# SUP_3_3_FMC.net
KiCad netlist of a schematic drawn in Altium Designer
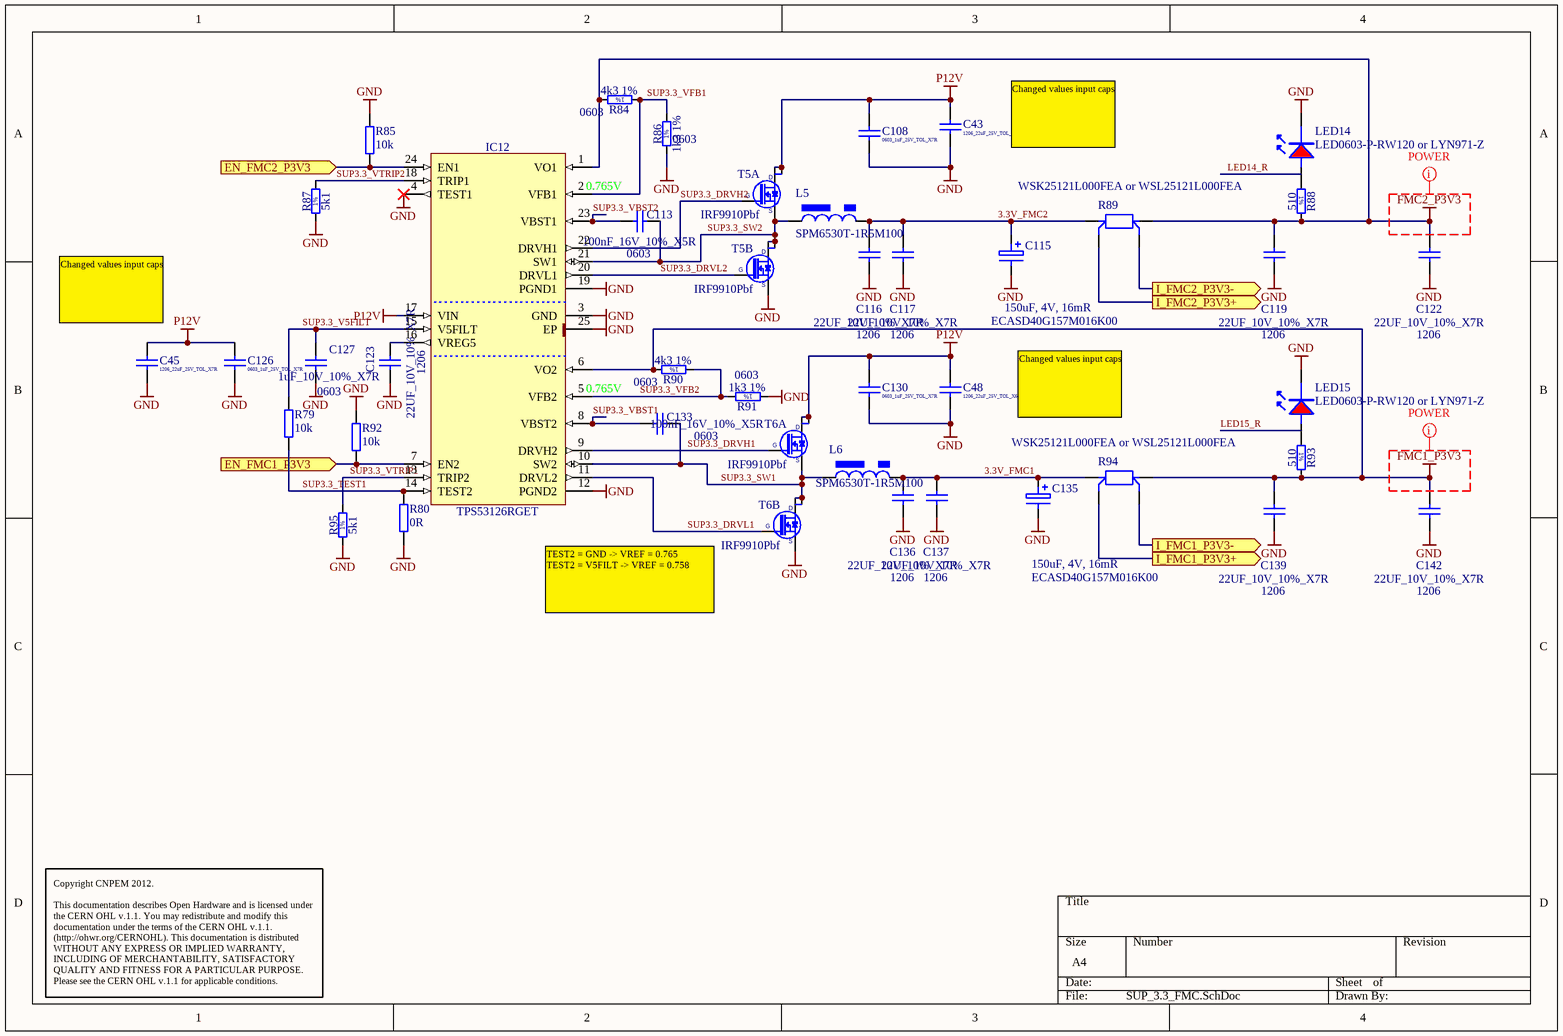
[diagram p0: SUP_3.3_FMC.SchDoc]

(export (version "E")
  (design (tool "Eeschema 10.0.6"))
  (components
    (comp (ref "C43")
      (value "1206_22uF_25V_TOL_X6S")
      (footprint "CAPC3225X140N")
      (fields (field (name "PART NUMBER") "Ceramic_1206"))
      (libsource (lib "Capacitors") (part "Capacitor"))
    )
    (comp (ref "C45")
      (value "1206_22uF_25V_TOL_X7R")
      (footprint "CAPC3225X140N")
      (fields (field (name "PART NUMBER") "Ceramic_1206"))
      (libsource (lib "Capacitors") (part "Capacitor"))
    )
    (comp (ref "C48")
      (value "1206_22uF_25V_TOL_X6S")
      (footprint "CAPC3225X140N")
      (fields (field (name "PART NUMBER") "Ceramic_1206"))
      (libsource (lib "Capacitors") (part "Capacitor"))
    )
    (comp (ref "C108")
      (value "0603_1uF_25V_TOL_X7R")
      (footprint "CAPC1608X90N")
      (fields (field (name "PART NUMBER") "Ceramic_0603"))
      (libsource (lib "Capacitors") (part "Capacitor"))
    )
    (comp (ref "C113")
      (value "100nF_16V_10%_X5R")
      (footprint "0402C")
      (description "Non-polarised capacitor")
      (fields
        (field (name "PART NUMBER") "CC0603_100NF_50V_10%_X7R")
        (field (name "VOLTAGE") "50V")
        (field (name "CASE") "0603")
        (field (name "AUTHOR") "CERN DEM JLC")
      )
      (libsource (lib "Capacitors") (part "Capacitor - non polarized"))
    )
    (comp (ref "C115")
      (value "ECASD40G157M016K00")
      (footprint "2917_POLY")
      (description "POLY, 150uF, 4V, ESR: 16mR")
      (fields (field (name "ALTIUM_VALUE") "150uF, 4V, 16mR"))
      (libsource (lib "LIBRARY_SCH") (part "CAP_POLYMER_SMDD"))
    )
    (comp (ref "C116")
      (value "22UF_10V_10%_X7R")
      (footprint "1206C")
      (description "Non-polarised capacitor")
      (fields
        (field (name "PART NUMBER") "CC1206_22UF_10V_10%_X7R")
        (field (name "VOLTAGE") "10V")
        (field (name "CASE") "1206")
        (field (name "AUTHOR") "CERN DEM JLC")
      )
      (libsource (lib "Capacitors") (part "Capacitor - non polarized"))
    )
    (comp (ref "C117")
      (value "22UF_10V_10%_X7R")
      (footprint "1206C")
      (description "Non-polarised capacitor")
      (fields
        (field (name "PART NUMBER") "CC1206_22UF_10V_10%_X7R")
        (field (name "VOLTAGE") "10V")
        (field (name "CASE") "1206")
        (field (name "AUTHOR") "CERN DEM JLC")
      )
      (libsource (lib "Capacitors") (part "Capacitor - non polarized"))
    )
    (comp (ref "C119")
      (value "22UF_10V_10%_X7R")
      (footprint "1206C")
      (description "Non-polarised capacitor")
      (fields
        (field (name "PART NUMBER") "CC1206_22UF_10V_10%_X7R")
        (field (name "VOLTAGE") "10V")
        (field (name "CASE") "1206")
        (field (name "AUTHOR") "CERN DEM JLC")
      )
      (libsource (lib "Capacitors") (part "Capacitor - non polarized"))
    )
    (comp (ref "C122")
      (value "22UF_10V_10%_X7R")
      (footprint "1206C")
      (description "Non-polarised capacitor")
      (fields
        (field (name "PART NUMBER") "CC1206_22UF_10V_10%_X7R")
        (field (name "VOLTAGE") "10V")
        (field (name "CASE") "1206")
        (field (name "AUTHOR") "CERN DEM JLC")
      )
      (libsource (lib "Capacitors") (part "Capacitor - non polarized"))
    )
    (comp (ref "C123")
      (value "22UF_10V_10%_X7R")
      (footprint "1206C")
      (description "Non-polarised capacitor")
      (fields
        (field (name "PART NUMBER") "CC1206_22UF_10V_10%_X7R")
        (field (name "VOLTAGE") "10V")
        (field (name "CASE") "1206")
        (field (name "AUTHOR") "CERN DEM JLC")
      )
      (libsource (lib "Capacitors") (part "Capacitor - non polarized"))
    )
    (comp (ref "C126")
      (value "0603_1uF_25V_TOL_X7R")
      (footprint "CAPC1608X90N")
      (fields (field (name "PART NUMBER") "Ceramic_0603"))
      (libsource (lib "Capacitors") (part "Capacitor"))
    )
    (comp (ref "C127")
      (value "1uF_10V_10%_X7R")
      (footprint "0603C")
      (description "Non-polarised capacitor")
      (fields
        (field (name "PART NUMBER") "CC0603_1UF_16V_10%_X7R")
        (field (name "VOLTAGE") "16V")
        (field (name "CASE") "0603")
        (field (name "AUTHOR") "CERN DEM JLC")
      )
      (libsource (lib "Capacitors") (part "Capacitor - non polarized"))
    )
    (comp (ref "C130")
      (value "0603_1uF_25V_TOL_X7R")
      (footprint "CAPC1608X90N")
      (fields (field (name "PART NUMBER") "Ceramic_0603"))
      (libsource (lib "Capacitors") (part "Capacitor"))
    )
    (comp (ref "C133")
      (value "100nF_16V_10%_X5R")
      (footprint "0402C")
      (description "Non-polarised capacitor")
      (fields
        (field (name "PART NUMBER") "CC0603_100NF_50V_10%_X7R")
        (field (name "VOLTAGE") "50V")
        (field (name "CASE") "0603")
        (field (name "AUTHOR") "CERN DEM JLC")
      )
      (libsource (lib "Capacitors") (part "Capacitor - non polarized"))
    )
    (comp (ref "C135")
      (value "ECASD40G157M016K00")
      (footprint "2917_POLY")
      (description "POLY, 150uF, 4V, ESR: 16mR")
      (fields (field (name "ALTIUM_VALUE") "150uF, 4V, 16mR"))
      (libsource (lib "LIBRARY_SCH") (part "CAP_POLYMER_SMDD"))
    )
    (comp (ref "C136")
      (value "22UF_10V_10%_X7R")
      (footprint "1206C")
      (description "Non-polarised capacitor")
      (fields
        (field (name "PART NUMBER") "CC1206_22UF_10V_10%_X7R")
        (field (name "VOLTAGE") "10V")
        (field (name "CASE") "1206")
        (field (name "AUTHOR") "CERN DEM JLC")
      )
      (libsource (lib "Capacitors") (part "Capacitor - non polarized"))
    )
    (comp (ref "C137")
      (value "22UF_10V_10%_X7R")
      (footprint "1206C")
      (description "Non-polarised capacitor")
      (fields
        (field (name "PART NUMBER") "CC1206_22UF_10V_10%_X7R")
        (field (name "VOLTAGE") "10V")
        (field (name "CASE") "1206")
        (field (name "AUTHOR") "CERN DEM JLC")
      )
      (libsource (lib "Capacitors") (part "Capacitor - non polarized"))
    )
    (comp (ref "C139")
      (value "22UF_10V_10%_X7R")
      (footprint "1206C")
      (description "Non-polarised capacitor")
      (fields
        (field (name "PART NUMBER") "CC1206_22UF_10V_10%_X7R")
        (field (name "VOLTAGE") "10V")
        (field (name "CASE") "1206")
        (field (name "AUTHOR") "CERN DEM JLC")
      )
      (libsource (lib "Capacitors") (part "Capacitor - non polarized"))
    )
    (comp (ref "C142")
      (value "22UF_10V_10%_X7R")
      (footprint "1206C")
      (description "Non-polarised capacitor")
      (fields
        (field (name "PART NUMBER") "CC1206_22UF_10V_10%_X7R")
        (field (name "VOLTAGE") "10V")
        (field (name "CASE") "1206")
        (field (name "AUTHOR") "CERN DEM JLC")
      )
      (libsource (lib "Capacitors") (part "Capacitor - non polarized"))
    )
    (comp (ref "IC12")
      (value "TPS53126RGET")
      (footprint "QFN50P400X400X100-25N-S255")
      (description "Dual Synchronous Step-Down Controller For Low Voltage Power Rails")
      (fields (field (name "MANUFACTURER") "TEXAS INSTRUMENTS") (field (name "AUTHOR") "CERN DEM JLC"))
      (libsource (lib "ICs And Semiconductors") (part "TPS53126RGET"))
    )
    (comp (ref "L5")
      (value "SPM6530T-1R5M100")
      (footprint "IND_TDK_SPM6530")
      (description "1.5uH, 20%, 10mR, 11.5A")
      (libsource (lib "LIBRARY_SCH") (part "L_POWER_SPM6530T"))
    )
    (comp (ref "L6")
      (value "SPM6530T-1R5M100")
      (footprint "IND_TDK_SPM6530")
      (description "1.5uH, 20%, 10mR, 11.5A")
      (libsource (lib "LIBRARY_SCH") (part "L_POWER_SPM6530T"))
    )
    (comp (ref "LED14")
      (value "LED0603-P-RW120 or LYN971-Z")
      (footprint "led_0603R")
      (description "LED 0603 red")
      (libsource (lib "LIBRARY_SCH") (part "LED_0603R"))
    )
    (comp (ref "LED15")
      (value "LED0603-P-RW120 or LYN971-Z")
      (footprint "led_0603R")
      (description "LED 0603 red")
      (libsource (lib "LIBRARY_SCH") (part "LED_0603R"))
    )
    (comp (ref "R79")
      (value "10k")
      (footprint "0402R")
      (description "SMD Resistor")
      (libsource (lib "LIBRARY_SCH") (part "RES_0402"))
    )
    (comp (ref "R80")
      (value "0R")
      (footprint "0402R")
      (description "SMD Resistor")
      (libsource (lib "LIBRARY_SCH") (part "RES_0402"))
    )
    (comp (ref "R84")
      (value "4k3 1%")
      (footprint "0603R")
      (description "Resistor - 1%")
      (fields
        (field (name "PART NUMBER") "R0603_4K3_1%_0.1W_100PPM")
        (field (name "POWER") "0.1W")
        (field (name "CASE") "0603")
        (field (name "AUTHOR") "CERN DEM JLC")
      )
      (libsource (lib "Resistors") (part "Resistor - 1%"))
    )
    (comp (ref "R85")
      (value "10k")
      (footprint "0402R")
      (description "SMD Resistor")
      (libsource (lib "LIBRARY_SCH") (part "RES_0402"))
    )
    (comp (ref "R86")
      (value "1k3 1%")
      (footprint "0603R")
      (description "Resistor - 1%")
      (fields
        (field (name "PART NUMBER") "R0603_1K3_1%_0.1W_100PPM")
        (field (name "POWER") "0.1W")
        (field (name "CASE") "0603")
        (field (name "AUTHOR") "CERN DEM JLC")
      )
      (libsource (lib "Resistors") (part "Resistor - 1%"))
    )
    (comp (ref "R87")
      (value "5k1")
      (footprint "0603R")
      (description "Resistor - 1%")
      (fields
        (field (name "PART NUMBER") "R0603_5K1_1%_0.1W_100PPM")
        (field (name "POWER") "0.1W")
        (field (name "AUTHOR") "CERN DEM JLC")
      )
      (libsource (lib "Resistors") (part "Resistor - 1%"))
    )
    (comp (ref "R88")
      (value "510")
      (footprint "0603R")
      (description "Resistor - 1%")
      (fields
        (field (name "PART NUMBER") "R0402_510R_1%_0.0625W_100PPM")
        (field (name "POWER") "0.0625W")
        (field (name "AUTHOR") "CERN DEM JLC")
      )
      (libsource (lib "Resistors") (part "Resistor - 1%"))
    )
    (comp (ref "R89")
      (value "WSK25121L000FEA or WSL25121L000FEA")
      (footprint "RES_WSK2512")
      (description "RESISTOR, METAL STRIP, 0.001 OHM 1%")
      (libsource (lib "LIBRARY_SCH") (part "RES_POW_Kelvin"))
    )
    (comp (ref "R90")
      (value "4k3 1%")
      (footprint "0603R")
      (description "Resistor - 1%")
      (fields
        (field (name "PART NUMBER") "R0603_4K3_1%_0.1W_100PPM")
        (field (name "POWER") "0.1W")
        (field (name "CASE") "0603")
        (field (name "AUTHOR") "CERN DEM JLC")
      )
      (libsource (lib "Resistors") (part "Resistor - 1%"))
    )
    (comp (ref "R91")
      (value "1k3 1%")
      (footprint "0603R")
      (description "Resistor - 1%")
      (fields
        (field (name "PART NUMBER") "R0603_1K3_1%_0.1W_100PPM")
        (field (name "POWER") "0.1W")
        (field (name "CASE") "0603")
        (field (name "AUTHOR") "CERN DEM JLC")
      )
      (libsource (lib "Resistors") (part "Resistor - 1%"))
    )
    (comp (ref "R92")
      (value "10k")
      (footprint "0402R")
      (description "SMD Resistor")
      (libsource (lib "LIBRARY_SCH") (part "RES_0402"))
    )
    (comp (ref "R93")
      (value "510")
      (footprint "0603R")
      (description "Resistor - 1%")
      (fields
        (field (name "PART NUMBER") "R0402_510R_1%_0.0625W_100PPM")
        (field (name "POWER") "0.0625W")
        (field (name "AUTHOR") "CERN DEM JLC")
      )
      (libsource (lib "Resistors") (part "Resistor - 1%"))
    )
    (comp (ref "R94")
      (value "WSK25121L000FEA or WSL25121L000FEA")
      (footprint "RES_WSK2512")
      (description "RESISTOR, METAL STRIP, 0.001 OHM 1%")
      (libsource (lib "LIBRARY_SCH") (part "RES_POW_Kelvin"))
    )
    (comp (ref "R95")
      (value "5k1")
      (footprint "0603R")
      (description "Resistor - 1%")
      (fields
        (field (name "PART NUMBER") "R0603_5K1_1%_0.1W_100PPM")
        (field (name "POWER") "0.1W")
        (field (name "AUTHOR") "CERN DEM JLC")
      )
      (libsource (lib "Resistors") (part "Resistor - 1%"))
    )
    (comp (ref "T5")
      (value "IRF9910Pbf")
      (footprint "SOIC127P600X175-8N")
      (description "Dual SO-8 MOSFET For POL Cconverter")
      (fields (field (name "MANUFACTURER") "INTERNATIONAL RECTIFIER") (field (name "AUTHOR") "CERN DEM JLC"))
      (libsource (lib "ICs And Semiconductors") (part "IRF9910"))
    )
    (comp (ref "T6")
      (value "IRF9910Pbf")
      (footprint "SOIC127P600X175-8N")
      (description "Dual SO-8 MOSFET For POL Cconverter")
      (fields (field (name "MANUFACTURER") "INTERNATIONAL RECTIFIER") (field (name "AUTHOR") "CERN DEM JLC"))
      (libsource (lib "ICs And Semiconductors") (part "IRF9910"))
    )
  )
  (nets
    (net (code "1") (name "/3.3V_FMC1") (class "Default")
      (node (ref "C135") (pin "1") (pinfunction "1_1") (pintype "passive"))
      (node (ref "C136") (pin "1") (pinfunction "1_1") (pintype "passive"))
      (node (ref "C137") (pin "1") (pinfunction "1_1") (pintype "passive"))
      (node (ref "L6") (pin "2") (pintype "passive"))
      (node (ref "R94") (pin "1") (pinfunction "1_1") (pintype "passive"))
    )
    (net (code "2") (name "/3.3V_FMC2") (class "Default")
      (node (ref "C115") (pin "1") (pinfunction "1_1") (pintype "passive"))
      (node (ref "C116") (pin "1") (pinfunction "1_1") (pintype "passive"))
      (node (ref "C117") (pin "1") (pinfunction "1_1") (pintype "passive"))
      (node (ref "L5") (pin "2") (pintype "passive"))
      (node (ref "R89") (pin "1") (pinfunction "1_1") (pintype "passive"))
    )
    (net (code "3") (name "/EN_FMC1_P3V3") (class "Default")
      (node (ref "IC12") (pin "7") (pinfunction "EN2_7") (pintype "input"))
      (node (ref "R92") (pin "1") (pinfunction "1_1") (pintype "passive"))
    )
    (net (code "4") (name "/EN_FMC2_P3V3") (class "Default")
      (node (ref "IC12") (pin "24") (pinfunction "EN1_24") (pintype "input"))
      (node (ref "R85") (pin "1") (pinfunction "1_1") (pintype "passive"))
    )
    (net (code "5") (name "/I_FMC1_P3V3+") (class "Default")
      (node (ref "R94") (pin "1a") (pinfunction "1a_1a") (pintype "passive"))
    )
    (net (code "6") (name "/I_FMC1_P3V3-") (class "Default")
      (node (ref "R94") (pin "2a") (pinfunction "2a_2a") (pintype "passive"))
    )
    (net (code "7") (name "/I_FMC2_P3V3+") (class "Default")
      (node (ref "R89") (pin "1a") (pinfunction "1a_1a") (pintype "passive"))
    )
    (net (code "8") (name "/I_FMC2_P3V3-") (class "Default")
      (node (ref "R89") (pin "2a") (pinfunction "2a_2a") (pintype "passive"))
    )
    (net (code "11") (name "/SUP3.3_DRVH1") (class "Default")
      (node (ref "IC12") (pin "9") (pinfunction "DRVH2_9") (pintype "output"))
      (node (ref "T6") (pin "4") (pinfunction "G_4") (pintype "passive"))
    )
    (net (code "12") (name "/SUP3.3_DRVH2") (class "Default")
      (node (ref "IC12") (pin "22") (pinfunction "DRVH1_22") (pintype "output"))
      (node (ref "T5") (pin "4") (pinfunction "G_4") (pintype "passive"))
    )
    (net (code "13") (name "/SUP3.3_DRVL1") (class "Default")
      (node (ref "IC12") (pin "11") (pinfunction "DRVL2_11") (pintype "output"))
      (node (ref "T6") (pin "2") (pinfunction "G_2") (pintype "passive"))
    )
    (net (code "14") (name "/SUP3.3_DRVL2") (class "Default")
      (node (ref "IC12") (pin "20") (pinfunction "DRVL1_20") (pintype "output"))
      (node (ref "T5") (pin "2") (pinfunction "G_2") (pintype "passive"))
    )
    (net (code "15") (name "/SUP3.3_SW1") (class "Default")
      (node (ref "C133") (pin "1") (pinfunction "1_1") (pintype "passive"))
      (node (ref "IC12") (pin "10") (pinfunction "SW2_10") (pintype "bidirectional"))
      (node (ref "L6") (pin "1") (pintype "passive"))
      (node (ref "T6") (pin "3") (pinfunction "S_3") (pintype "passive"))
      (node (ref "T6") (pin "7") (pinfunction "D_7") (pintype "passive"))
      (node (ref "T6") (pin "8") (pinfunction "D_8") (pintype "passive"))
    )
    (net (code "16") (name "/SUP3.3_SW2") (class "Default")
      (node (ref "C113") (pin "1") (pinfunction "1_1") (pintype "passive"))
      (node (ref "IC12") (pin "21") (pinfunction "SW1_21") (pintype "bidirectional"))
      (node (ref "L5") (pin "1") (pintype "passive"))
      (node (ref "T5") (pin "3") (pinfunction "S_3") (pintype "passive"))
      (node (ref "T5") (pin "7") (pinfunction "D_7") (pintype "passive"))
      (node (ref "T5") (pin "8") (pinfunction "D_8") (pintype "passive"))
    )
    (net (code "17") (name "/SUP3.3_TEST1") (class "Default")
      (node (ref "IC12") (pin "14") (pinfunction "TEST2_14") (pintype "input"))
      (node (ref "R79") (pin "1") (pinfunction "1_1") (pintype "passive"))
      (node (ref "R80") (pin "2") (pinfunction "2_2") (pintype "passive"))
    )
    (net (code "18") (name "/SUP3.3_V5FILT") (class "Default")
      (node (ref "C127") (pin "2") (pinfunction "2_2") (pintype "passive"))
      (node (ref "IC12") (pin "15") (pinfunction "V5FILT_15") (pintype "input"))
      (node (ref "R79") (pin "2") (pinfunction "2_2") (pintype "passive"))
    )
    (net (code "19") (name "/SUP3.3_VBST1") (class "Default")
      (node (ref "C133") (pin "2") (pinfunction "2_2") (pintype "passive"))
      (node (ref "IC12") (pin "8") (pinfunction "VBST2_8") (pintype "input"))
    )
    (net (code "20") (name "/SUP3.3_VBST2") (class "Default")
      (node (ref "C113") (pin "2") (pinfunction "2_2") (pintype "passive"))
      (node (ref "IC12") (pin "23") (pinfunction "VBST1_23") (pintype "input"))
    )
    (net (code "21") (name "/SUP3.3_VFB1") (class "Default")
      (node (ref "IC12") (pin "2") (pinfunction "VFB1_2") (pintype "input"))
      (node (ref "R84") (pin "1") (pinfunction "1_1") (pintype "passive"))
      (node (ref "R86") (pin "2") (pinfunction "2_2") (pintype "passive"))
    )
    (net (code "22") (name "/SUP3.3_VFB2") (class "Default")
      (node (ref "IC12") (pin "5") (pinfunction "VFB2_5") (pintype "input"))
      (node (ref "R90") (pin "1") (pinfunction "1_1") (pintype "passive"))
      (node (ref "R91") (pin "2") (pinfunction "2_2") (pintype "passive"))
    )
    (net (code "23") (name "/SUP3.3_VTRIP1") (class "Default")
      (node (ref "IC12") (pin "13") (pinfunction "TRIP2_13") (pintype "input"))
      (node (ref "R95") (pin "2") (pinfunction "2_2") (pintype "passive"))
    )
    (net (code "24") (name "/SUP3.3_VTRIP2") (class "Default")
      (node (ref "IC12") (pin "18") (pinfunction "TRIP1_18") (pintype "input"))
      (node (ref "R87") (pin "2") (pinfunction "2_2") (pintype "passive"))
    )
    (net (code "25") (name "FMC1_P3V3") (class "Default")
      (node (ref "C139") (pin "1") (pinfunction "1_1") (pintype "passive"))
      (node (ref "C142") (pin "1") (pinfunction "1_1") (pintype "passive"))
      (node (ref "IC12") (pin "6") (pinfunction "VO2_6") (pintype "input"))
      (node (ref "R90") (pin "2") (pinfunction "2_2") (pintype "passive"))
      (node (ref "R93") (pin "2") (pinfunction "2_2") (pintype "passive"))
      (node (ref "R94") (pin "2") (pinfunction "2_2") (pintype "passive"))
    )
    (net (code "26") (name "FMC2_P3V3") (class "Default")
      (node (ref "C119") (pin "1") (pinfunction "1_1") (pintype "passive"))
      (node (ref "C122") (pin "1") (pinfunction "1_1") (pintype "passive"))
      (node (ref "IC12") (pin "1") (pinfunction "VO1_1") (pintype "input"))
      (node (ref "R84") (pin "2") (pinfunction "2_2") (pintype "passive"))
      (node (ref "R88") (pin "2") (pinfunction "2_2") (pintype "passive"))
      (node (ref "R89") (pin "2") (pinfunction "2_2") (pintype "passive"))
    )
    (net (code "27") (name "GND") (class "Default")
      (node (ref "C108") (pin "1") (pinfunction "1_1") (pintype "passive"))
      (node (ref "C115") (pin "2") (pinfunction "2_2") (pintype "passive"))
      (node (ref "C116") (pin "2") (pinfunction "2_2") (pintype "passive"))
      (node (ref "C117") (pin "2") (pinfunction "2_2") (pintype "passive"))
      (node (ref "C119") (pin "2") (pinfunction "2_2") (pintype "passive"))
      (node (ref "C122") (pin "2") (pinfunction "2_2") (pintype "passive"))
      (node (ref "C123") (pin "1") (pinfunction "1_1") (pintype "passive"))
      (node (ref "C126") (pin "1") (pinfunction "1_1") (pintype "passive"))
      (node (ref "C127") (pin "1") (pinfunction "1_1") (pintype "passive"))
      (node (ref "C130") (pin "1") (pinfunction "1_1") (pintype "passive"))
      (node (ref "C135") (pin "2") (pinfunction "2_2") (pintype "passive"))
      (node (ref "C136") (pin "2") (pinfunction "2_2") (pintype "passive"))
      (node (ref "C137") (pin "2") (pinfunction "2_2") (pintype "passive"))
      (node (ref "C139") (pin "2") (pinfunction "2_2") (pintype "passive"))
      (node (ref "C142") (pin "2") (pinfunction "2_2") (pintype "passive"))
      (node (ref "C43") (pin "1") (pinfunction "1_1") (pintype "passive"))
      (node (ref "C45") (pin "1") (pinfunction "1_1") (pintype "passive"))
      (node (ref "C48") (pin "1") (pinfunction "1_1") (pintype "passive"))
      (node (ref "IC12") (pin "12") (pinfunction "PGND2_12") (pintype "power_in"))
      (node (ref "IC12") (pin "19") (pinfunction "PGND1_19") (pintype "power_in"))
      (node (ref "IC12") (pin "25") (pinfunction "EP_25") (pintype "power_in"))
      (node (ref "IC12") (pin "3") (pinfunction "GND_3") (pintype "power_in"))
      (node (ref "IC12") (pin "4") (pinfunction "TEST1_4") (pintype "output"))
      (node (ref "LED14") (pin "K") (pinfunction "K_K") (pintype "passive"))
      (node (ref "LED15") (pin "K") (pinfunction "K_K") (pintype "passive"))
      (node (ref "R80") (pin "1") (pinfunction "1_1") (pintype "passive"))
      (node (ref "R85") (pin "2") (pinfunction "2_2") (pintype "passive"))
      (node (ref "R86") (pin "1") (pinfunction "1_1") (pintype "passive"))
      (node (ref "R87") (pin "1") (pinfunction "1_1") (pintype "passive"))
      (node (ref "R91") (pin "1") (pinfunction "1_1") (pintype "passive"))
      (node (ref "R92") (pin "2") (pinfunction "2_2") (pintype "passive"))
      (node (ref "R95") (pin "1") (pinfunction "1_1") (pintype "passive"))
      (node (ref "T5") (pin "1") (pinfunction "S_1") (pintype "passive"))
      (node (ref "T6") (pin "1") (pinfunction "S_1") (pintype "passive"))
    )
    (net (code "28") (name "Net-(IC12-VREG5)") (class "Default")
      (node (ref "C123") (pin "2") (pinfunction "2_2") (pintype "passive"))
      (node (ref "IC12") (pin "16") (pinfunction "VREG5_16") (pintype "output"))
    )
    (net (code "29") (name "Net-(LED14-PadA)") (class "Default")
      (node (ref "LED14") (pin "A") (pinfunction "A_A") (pintype "passive"))
      (node (ref "R88") (pin "1") (pinfunction "1_1") (pintype "passive"))
    )
    (net (code "30") (name "Net-(LED15-PadA)") (class "Default")
      (node (ref "LED15") (pin "A") (pinfunction "A_A") (pintype "passive"))
      (node (ref "R93") (pin "1") (pinfunction "1_1") (pintype "passive"))
    )
    (net (code "31") (name "P12V") (class "Default")
      (node (ref "C108") (pin "2") (pinfunction "2_2") (pintype "passive"))
      (node (ref "C126") (pin "2") (pinfunction "2_2") (pintype "passive"))
      (node (ref "C130") (pin "2") (pinfunction "2_2") (pintype "passive"))
      (node (ref "C43") (pin "2") (pinfunction "2_2") (pintype "passive"))
      (node (ref "C45") (pin "2") (pinfunction "2_2") (pintype "passive"))
      (node (ref "C48") (pin "2") (pinfunction "2_2") (pintype "passive"))
      (node (ref "IC12") (pin "17") (pinfunction "VIN_17") (pintype "input"))
      (node (ref "T5") (pin "5") (pinfunction "D_5") (pintype "passive"))
      (node (ref "T5") (pin "6") (pinfunction "D_6") (pintype "passive"))
      (node (ref "T6") (pin "5") (pinfunction "D_5") (pintype "passive"))
      (node (ref "T6") (pin "6") (pinfunction "D_6") (pintype "passive"))
    )
  )
)
